# 50x80_Crystal_Filter_with_Amp.net
KiCad netlist of a schematic drawn in Altium Designer
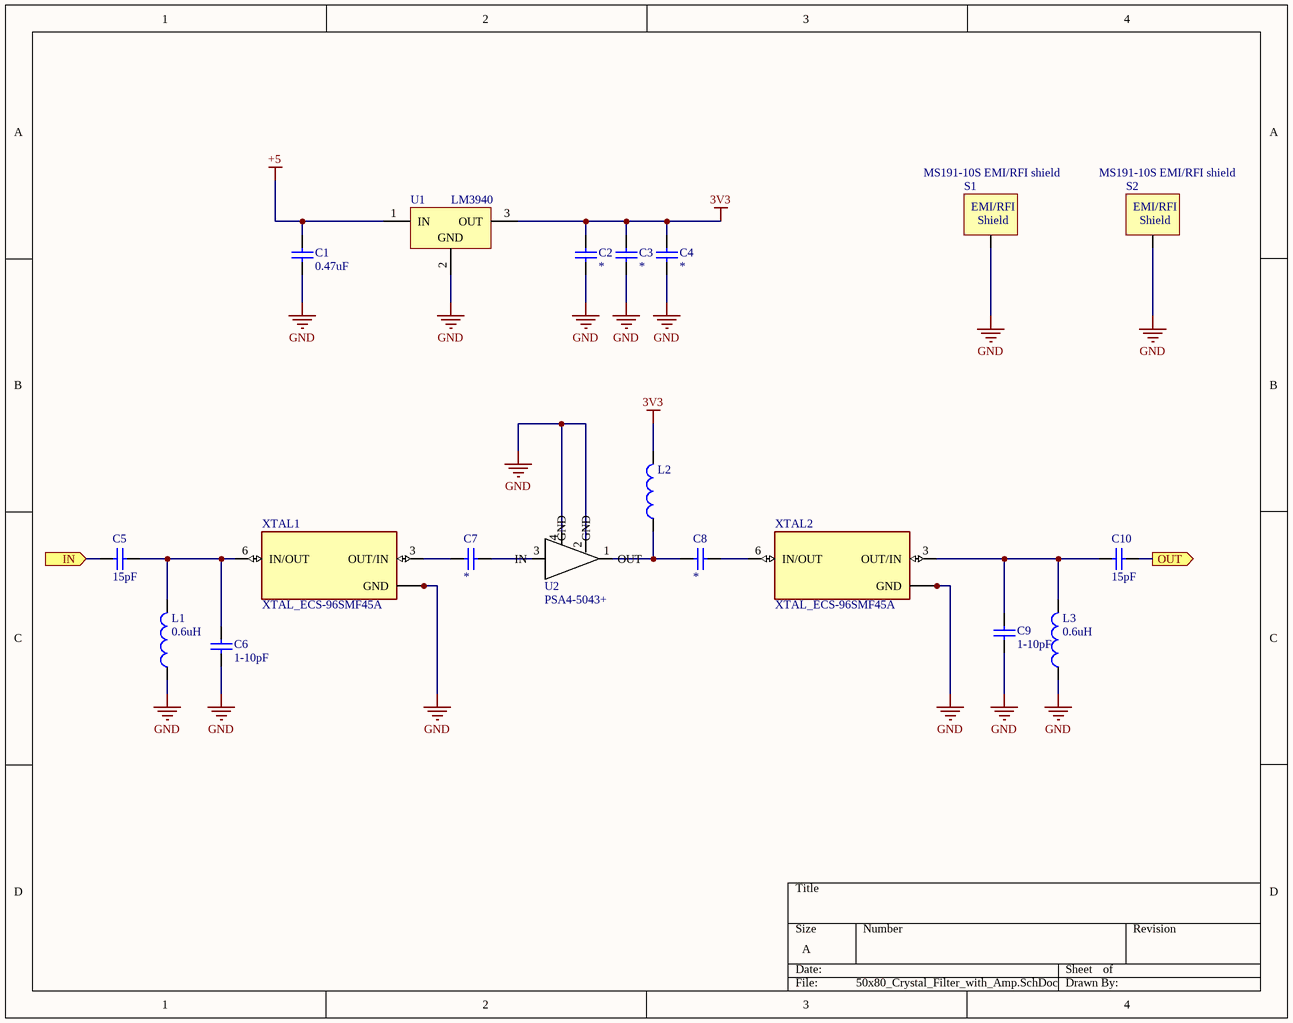
[diagram p0: 50x80_Crystal_Filter_with_Amp.SchDoc]

(export (version "E")
  (design (tool "Eeschema 10.0.6"))
  (components
    (comp (ref "C1")
      (value "0.47uF")
      (footprint "0805")
      (description "ABE_Capacitor")
      (fields (field (name "Comment") "Cap_0805"))
      (libsource (lib "Schlib1") (part "Cap_0805"))
    )
    (comp (ref "C2")
      (value "Cap_1206")
      (footprint "1206")
      (description "ABE_Capacitor")
      (fields (field (name "ALTIUM_VALUE") "*"))
      (libsource (lib "Schlib1") (part "Cap_1206"))
    )
    (comp (ref "C3")
      (value "Cap_1206")
      (footprint "1206")
      (description "ABE_Capacitor")
      (fields (field (name "ALTIUM_VALUE") "*"))
      (libsource (lib "Schlib1") (part "Cap_1206"))
    )
    (comp (ref "C4")
      (value "Cap_1206")
      (footprint "1206")
      (description "ABE_Capacitor")
      (fields (field (name "ALTIUM_VALUE") "*"))
      (libsource (lib "Schlib1") (part "Cap_1206"))
    )
    (comp (ref "C5")
      (value "15pF")
      (footprint "0805")
      (description "ABE_Capacitor")
      (fields (field (name "Comment") "Cap_0805"))
      (libsource (lib "Schlib1") (part "Cap_0805"))
    )
    (comp (ref "C6")
      (value "1-10pF")
      (footprint "0805")
      (description "ABE_Capacitor")
      (fields (field (name "Comment") "Cap_0805"))
      (libsource (lib "Schlib1") (part "Cap_0805"))
    )
    (comp (ref "C7")
      (value "Cap_1206")
      (footprint "1206")
      (description "ABE_Capacitor")
      (fields (field (name "ALTIUM_VALUE") "*"))
      (libsource (lib "Schlib1") (part "Cap_1206"))
    )
    (comp (ref "C8")
      (value "Cap_1206")
      (footprint "1206")
      (description "ABE_Capacitor")
      (fields (field (name "ALTIUM_VALUE") "*"))
      (libsource (lib "Schlib1") (part "Cap_1206"))
    )
    (comp (ref "C9")
      (value "1-10pF")
      (footprint "0805")
      (description "ABE_Capacitor")
      (fields (field (name "Comment") "Cap_0805"))
      (libsource (lib "Schlib1") (part "Cap_0805"))
    )
    (comp (ref "C10")
      (value "15pF")
      (footprint "0805")
      (description "ABE_Capacitor")
      (fields (field (name "Comment") "Cap_0805"))
      (libsource (lib "Schlib1") (part "Cap_0805"))
    )
    (comp (ref "L1")
      (value "0.6uH")
      (footprint "0805")
      (description "ABE_Inductor")
      (fields (field (name "Comment") "IND_0805"))
      (libsource (lib "Schlib1") (part "IND_0805"))
    )
    (comp (ref "L2")
      (value "IND_1206")
      (footprint "1206")
      (description "ABE_Inductor")
      (libsource (lib "Schlib1") (part "IND_1206"))
    )
    (comp (ref "L3")
      (value "0.6uH")
      (footprint "0805")
      (description "ABE_Inductor")
      (fields (field (name "Comment") "IND_0805"))
      (libsource (lib "Schlib1") (part "IND_0805"))
    )
    (comp (ref "S1")
      (value "MS191-10S EMI/RFI shield")
      (footprint "MS191-10S")
      (description "EMI/RFI shield MS191-10S")
      (libsource (lib "Schlib1") (part "MS191-10S"))
    )
    (comp (ref "S2")
      (value "MS191-10S EMI/RFI shield")
      (footprint "MS191-10S")
      (description "EMI/RFI shield MS191-10S")
      (libsource (lib "Schlib1") (part "MS191-10S"))
    )
    (comp (ref "U1")
      (value "LM3940")
      (footprint "TI-DCY4_N")
      (description "3-Terminal Positive Regulator")
      (libsource (lib "Schlib1") (part "LM3940"))
    )
    (comp (ref "U2")
      (value "PSA4-5043+")
      (footprint "PSA4-5043+")
      (libsource (lib "Schlib1") (part "PSA4-5043+"))
    )
    (comp (ref "XTAL1")
      (value "XTAL_ECS-96SMF45A")
      (footprint "XTAL_ECS-96SMF45A30-TR")
      (description "45MHz SMD Crystal Filter")
      (libsource (lib "Schlib1") (part "XTAL_ECS-96SMF45A"))
    )
    (comp (ref "XTAL2")
      (value "XTAL_ECS-96SMF45A")
      (footprint "XTAL_ECS-96SMF45A30-TR")
      (description "45MHz SMD Crystal Filter")
      (libsource (lib "Schlib1") (part "XTAL_ECS-96SMF45A"))
    )
  )
  (nets
    (net (code "1") (name "+5") (class "Default")
      (node (ref "C1") (pin "2") (pinfunction "2_2") (pintype "passive"))
      (node (ref "U1") (pin "1") (pinfunction "IN_1") (pintype "power_in"))
    )
    (net (code "2") (name "/IN") (class "Default")
      (node (ref "C5") (pin "1") (pinfunction "1_1") (pintype "passive"))
    )
    (net (code "3") (name "/OUT") (class "Default")
      (node (ref "C10") (pin "2") (pinfunction "2_2") (pintype "passive"))
    )
    (net (code "4") (name "3V3") (class "Default")
      (node (ref "C2") (pin "1") (pinfunction "1_1") (pintype "passive"))
      (node (ref "C3") (pin "1") (pinfunction "1_1") (pintype "passive"))
      (node (ref "C4") (pin "1") (pinfunction "1_1") (pintype "passive"))
      (node (ref "L2") (pin "2") (pinfunction "2_2") (pintype "passive"))
      (node (ref "U1") (pin "3") (pinfunction "OUT_3") (pintype "power_in"))
    )
    (net (code "5") (name "GND") (class "Default")
      (node (ref "C1") (pin "1") (pinfunction "1_1") (pintype "passive"))
      (node (ref "C2") (pin "2") (pinfunction "2_2") (pintype "passive"))
      (node (ref "C3") (pin "2") (pinfunction "2_2") (pintype "passive"))
      (node (ref "C4") (pin "2") (pinfunction "2_2") (pintype "passive"))
      (node (ref "C6") (pin "1") (pinfunction "1_1") (pintype "passive"))
      (node (ref "C9") (pin "1") (pinfunction "1_1") (pintype "passive"))
      (node (ref "L1") (pin "1") (pinfunction "1_1") (pintype "passive"))
      (node (ref "L3") (pin "1") (pinfunction "1_1") (pintype "passive"))
      (node (ref "S1") (pin "0") (pintype "passive"))
      (node (ref "S2") (pin "0") (pintype "passive"))
      (node (ref "U1") (pin "2") (pinfunction "GND_2") (pintype "power_in"))
      (node (ref "U2") (pin "2") (pinfunction "GND_2") (pintype "passive"))
      (node (ref "U2") (pin "4") (pinfunction "GND_4") (pintype "passive"))
      (node (ref "XTAL1") (pin "1") (pinfunction "GND_1") (pintype "power_in"))
      (node (ref "XTAL1") (pin "2") (pinfunction "GND_2") (pintype "power_in"))
      (node (ref "XTAL1") (pin "4") (pinfunction "GND_4") (pintype "power_in"))
      (node (ref "XTAL1") (pin "5") (pinfunction "GND_5") (pintype "power_in"))
      (node (ref "XTAL2") (pin "1") (pinfunction "GND_1") (pintype "power_in"))
      (node (ref "XTAL2") (pin "2") (pinfunction "GND_2") (pintype "power_in"))
      (node (ref "XTAL2") (pin "4") (pinfunction "GND_4") (pintype "power_in"))
      (node (ref "XTAL2") (pin "5") (pinfunction "GND_5") (pintype "power_in"))
    )
    (net (code "6") (name "Net-(U2-IN)") (class "Default")
      (node (ref "C7") (pin "2") (pinfunction "2_2") (pintype "passive"))
      (node (ref "U2") (pin "3") (pinfunction "IN_3") (pintype "passive"))
    )
    (net (code "7") (name "Net-(U2-OUT)") (class "Default")
      (node (ref "C8") (pin "1") (pinfunction "1_1") (pintype "passive"))
      (node (ref "L2") (pin "1") (pinfunction "1_1") (pintype "passive"))
      (node (ref "U2") (pin "1") (pinfunction "OUT_1") (pintype "passive"))
    )
    (net (code "8") (name "Net-(XTAL1-IN{slash}OUT)") (class "Default")
      (node (ref "C5") (pin "2") (pinfunction "2_2") (pintype "passive"))
      (node (ref "C6") (pin "2") (pinfunction "2_2") (pintype "passive"))
      (node (ref "L1") (pin "2") (pinfunction "2_2") (pintype "passive"))
      (node (ref "XTAL1") (pin "6") (pinfunction "IN/OUT_6") (pintype "bidirectional"))
    )
    (net (code "9") (name "Net-(XTAL1-OUT{slash}IN)") (class "Default")
      (node (ref "C7") (pin "1") (pinfunction "1_1") (pintype "passive"))
      (node (ref "XTAL1") (pin "3") (pinfunction "OUT/IN_3") (pintype "bidirectional"))
    )
    (net (code "10") (name "Net-(XTAL2-IN{slash}OUT)") (class "Default")
      (node (ref "C8") (pin "2") (pinfunction "2_2") (pintype "passive"))
      (node (ref "XTAL2") (pin "6") (pinfunction "IN/OUT_6") (pintype "bidirectional"))
    )
    (net (code "11") (name "Net-(XTAL2-OUT{slash}IN)") (class "Default")
      (node (ref "C10") (pin "1") (pinfunction "1_1") (pintype "passive"))
      (node (ref "C9") (pin "2") (pinfunction "2_2") (pintype "passive"))
      (node (ref "L3") (pin "2") (pinfunction "2_2") (pintype "passive"))
      (node (ref "XTAL2") (pin "3") (pinfunction "OUT/IN_3") (pintype "bidirectional"))
    )
  )
)
